# eeZeeSwitch.net
KiCad netlist of a schematic drawn in EAGLE
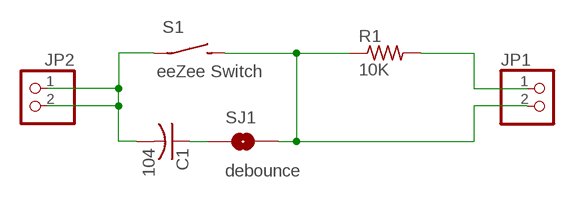
[diagram p0: schematic, sheet 1]

(export (version "E")
  (design (tool "Eeschema 10.0.6"))
  (components
    (comp (ref "C1")
      (value "104")
      (footprint "eagle-import:C0603")
      (libsource (lib "eagle-import") (part "C-USC0603"))
    )
    (comp (ref "JP1")
      (value "PINHD-1X02_2.54-S")
      (footprint "eagle-import:1X02-S")
      (libsource (lib "eagle-import") (part "PINHD-1X02_2.54-S"))
    )
    (comp (ref "JP2")
      (value "PINHD-1X02_2.54-S")
      (footprint "eagle-import:1X02-S")
      (libsource (lib "eagle-import") (part "PINHD-1X02_2.54-S"))
    )
    (comp (ref "R1")
      (value "10K")
      (footprint "eagle-import:R0603")
      (libsource (lib "eagle-import") (part "R-US_R0603"))
    )
    (comp (ref "S1")
      (value "eeZee Switch")
      (footprint "eagle-import:6MMTACTILE_RECT")
      (libsource (lib "eagle-import") (part "SPST_TAC_RECT1"))
    )
    (comp (ref "SJ1")
      (value "debounce")
      (footprint "eagle-import:SJ_2S-NO")
      (libsource (lib "eagle-import") (part "SOLDERJUMPERNO"))
    )
  )
  (nets
    (net (code "1") (name "Net-(C1-Pad1)") (class "Default")
      (node (ref "C1") (pin "1") (pinfunction "1_1") (pintype "passive"))
      (node (ref "SJ1") (pin "1") (pinfunction "1_1") (pintype "passive"))
    )
    (net (code "2") (name "Net-(JP1-Pad1)") (class "Default")
      (node (ref "JP1") (pin "1") (pinfunction "1_1") (pintype "passive"))
      (node (ref "R1") (pin "2") (pinfunction "2_2") (pintype "passive"))
    )
    (net (code "3") (name "Net-(S1-P)") (class "Default")
      (node (ref "C1") (pin "2") (pinfunction "2_2") (pintype "passive"))
      (node (ref "JP2") (pin "1") (pinfunction "1_1") (pintype "passive"))
      (node (ref "JP2") (pin "2") (pinfunction "2_2") (pintype "passive"))
      (node (ref "S1") (pin "P$1") (pinfunction "P_P$1") (pintype "passive"))
    )
    (net (code "4") (name "Net-(S1-S)") (class "Default")
      (node (ref "JP1") (pin "2") (pinfunction "2_2") (pintype "passive"))
      (node (ref "R1") (pin "1") (pinfunction "1_1") (pintype "passive"))
      (node (ref "S1") (pin "P$2") (pinfunction "S_P$2") (pintype "passive"))
      (node (ref "SJ1") (pin "2") (pinfunction "2_2") (pintype "passive"))
    )
  )
)
